# msp432_breakout_i2c.net
KiCad netlist of a schematic drawn in EAGLE
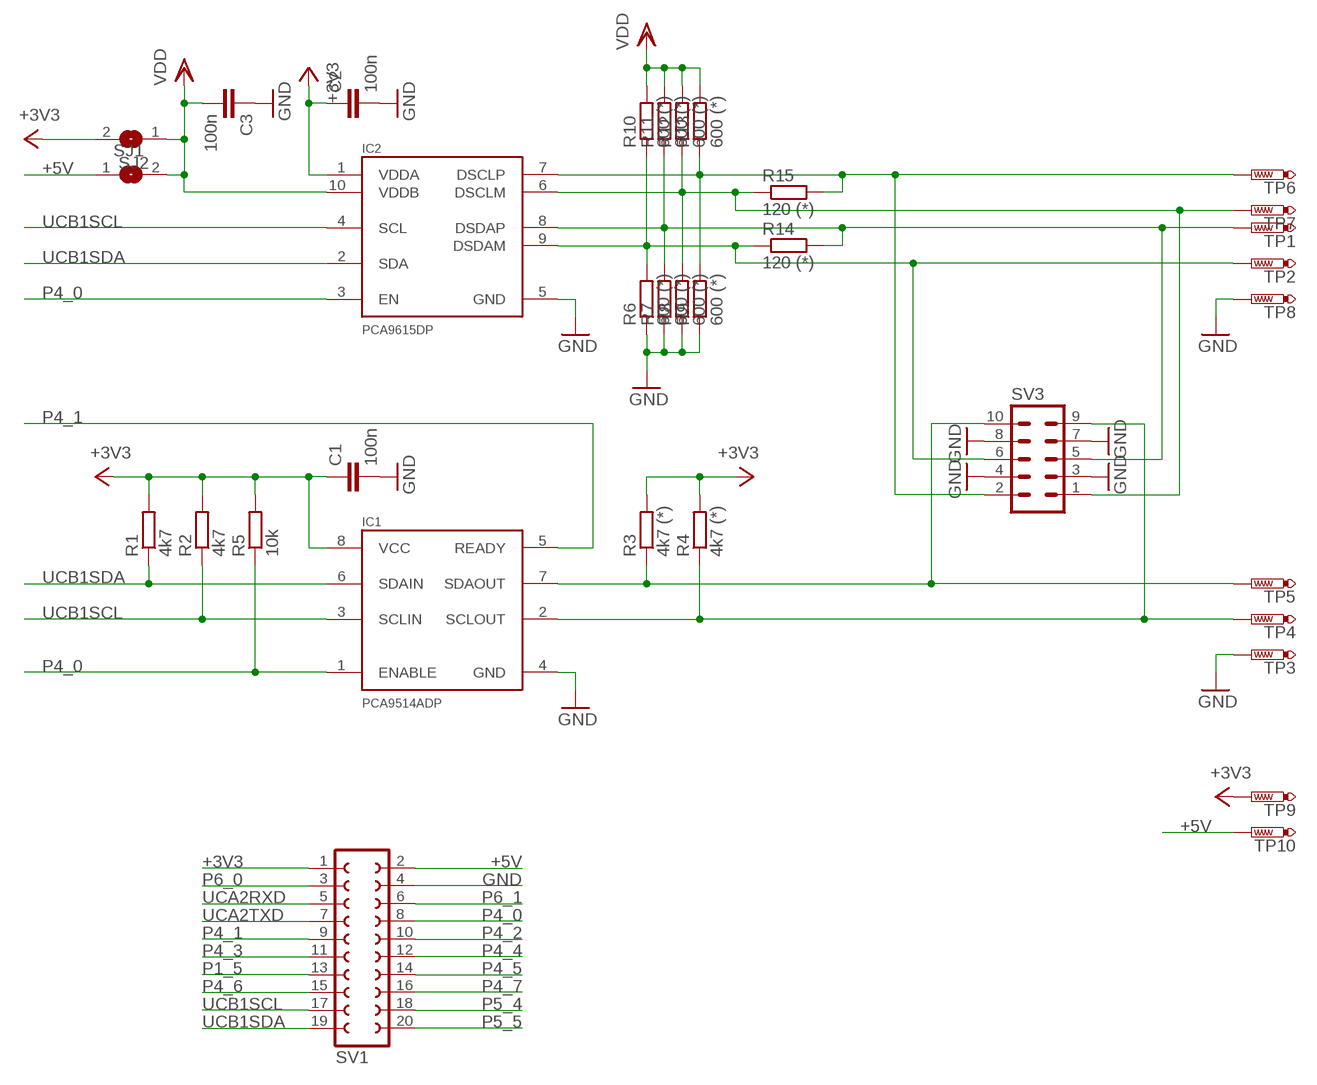
[diagram p0: schematic, sheet 1]

(export (version "E")
  (design (tool "Eeschema 10.0.6"))
  (components
    (comp (ref "C1")
      (value "100n")
      (footprint "eagle-import:C0603")
      (libsource (lib "eagle-import") (part "C-EUC0603"))
    )
    (comp (ref "C2")
      (value "100n")
      (footprint "eagle-import:C0603")
      (libsource (lib "eagle-import") (part "C-EUC0603"))
    )
    (comp (ref "C3")
      (value "100n")
      (footprint "eagle-import:C0603")
      (libsource (lib "eagle-import") (part "C-EUC0603"))
    )
    (comp (ref "IC1")
      (value "PCA9514ADP")
      (footprint "eagle-import:TSSOP8")
      (libsource (lib "eagle-import") (part "PCA9514ADP"))
    )
    (comp (ref "IC2")
      (value "PCA9615DP")
      (footprint "eagle-import:TSSOP10")
      (libsource (lib "eagle-import") (part "PCA9615DP"))
    )
    (comp (ref "R1")
      (value "4k7")
      (footprint "eagle-import:R0603")
      (libsource (lib "eagle-import") (part "R-EU_R0603"))
    )
    (comp (ref "R2")
      (value "4k7")
      (footprint "eagle-import:R0603")
      (libsource (lib "eagle-import") (part "R-EU_R0603"))
    )
    (comp (ref "R3")
      (value "4k7 (*)")
      (footprint "eagle-import:R0603")
      (libsource (lib "eagle-import") (part "R-EU_R0603"))
    )
    (comp (ref "R4")
      (value "4k7 (*)")
      (footprint "eagle-import:R0603")
      (libsource (lib "eagle-import") (part "R-EU_R0603"))
    )
    (comp (ref "R5")
      (value "10k")
      (footprint "eagle-import:R0603")
      (libsource (lib "eagle-import") (part "R-EU_R0603"))
    )
    (comp (ref "R6")
      (value "600 (*)")
      (footprint "eagle-import:R0603")
      (libsource (lib "eagle-import") (part "R-EU_R0603"))
    )
    (comp (ref "R7")
      (value "600 (*)")
      (footprint "eagle-import:R0603")
      (libsource (lib "eagle-import") (part "R-EU_R0603"))
    )
    (comp (ref "R8")
      (value "600 (*)")
      (footprint "eagle-import:R0603")
      (libsource (lib "eagle-import") (part "R-EU_R0603"))
    )
    (comp (ref "R9")
      (value "600 (*)")
      (footprint "eagle-import:R0603")
      (libsource (lib "eagle-import") (part "R-EU_R0603"))
    )
    (comp (ref "R10")
      (value "600 (*)")
      (footprint "eagle-import:R0603")
      (libsource (lib "eagle-import") (part "R-EU_R0603"))
    )
    (comp (ref "R11")
      (value "600 (*)")
      (footprint "eagle-import:R0603")
      (libsource (lib "eagle-import") (part "R-EU_R0603"))
    )
    (comp (ref "R12")
      (value "600 (*)")
      (footprint "eagle-import:R0603")
      (libsource (lib "eagle-import") (part "R-EU_R0603"))
    )
    (comp (ref "R13")
      (value "600 (*)")
      (footprint "eagle-import:R0603")
      (libsource (lib "eagle-import") (part "R-EU_R0603"))
    )
    (comp (ref "R14")
      (value "120 (*)")
      (footprint "eagle-import:R0603")
      (libsource (lib "eagle-import") (part "R-EU_R0603"))
    )
    (comp (ref "R15")
      (value "120 (*)")
      (footprint "eagle-import:R0603")
      (libsource (lib "eagle-import") (part "R-EU_R0603"))
    )
    (comp (ref "SJ1") (value "SJ") (footprint "eagle-import:SJ") (libsource (lib "eagle-import") (part "SJ")))
    (comp (ref "SJ2") (value "SJ") (footprint "eagle-import:SJ") (libsource (lib "eagle-import") (part "SJ")))
    (comp (ref "SV1")
      (value "FE10-2")
      (footprint "eagle-import:FE10-2")
      (libsource (lib "eagle-import") (part "FE10-2"))
    )
    (comp (ref "SV3")
      (value "ML10")
      (footprint "eagle-import:ML10")
      (libsource (lib "eagle-import") (part "ML10"))
    )
    (comp (ref "TP1")
      (value "DSDAP")
      (footprint "eagle-import:P1-17")
      (libsource (lib "eagle-import") (part "PTR1PAD1-17"))
    )
    (comp (ref "TP2")
      (value "DSDAM")
      (footprint "eagle-import:P1-17")
      (libsource (lib "eagle-import") (part "PTR1PAD1-17"))
    )
    (comp (ref "TP3")
      (value "GND")
      (footprint "eagle-import:P1-17")
      (libsource (lib "eagle-import") (part "PTR1PAD1-17"))
    )
    (comp (ref "TP4")
      (value "SCLOUT")
      (footprint "eagle-import:P1-17")
      (libsource (lib "eagle-import") (part "PTR1PAD1-17"))
    )
    (comp (ref "TP5")
      (value "SDAOUT")
      (footprint "eagle-import:P1-17")
      (libsource (lib "eagle-import") (part "PTR1PAD1-17"))
    )
    (comp (ref "TP6")
      (value "DSCLP")
      (footprint "eagle-import:P1-17")
      (libsource (lib "eagle-import") (part "PTR1PAD1-17"))
    )
    (comp (ref "TP7")
      (value "DSCLM")
      (footprint "eagle-import:P1-17")
      (libsource (lib "eagle-import") (part "PTR1PAD1-17"))
    )
    (comp (ref "TP8")
      (value "GND")
      (footprint "eagle-import:P1-17")
      (libsource (lib "eagle-import") (part "PTR1PAD1-17"))
    )
    (comp (ref "TP9")
      (value "3V3")
      (footprint "eagle-import:P1-17")
      (libsource (lib "eagle-import") (part "PTR1PAD1-17"))
    )
    (comp (ref "TP10")
      (value "5V")
      (footprint "eagle-import:P1-17")
      (libsource (lib "eagle-import") (part "PTR1PAD1-17"))
    )
  )
  (nets
    (net (code "1") (name "+3V3") (class "Default")
      (node (ref "C1") (pin "1") (pinfunction "1_1") (pintype "passive"))
      (node (ref "C2") (pin "1") (pinfunction "1_1") (pintype "passive"))
      (node (ref "IC1") (pin "8") (pinfunction "VCC_8") (pintype "power_in"))
      (node (ref "IC2") (pin "1") (pinfunction "VDDA_1") (pintype "power_in"))
      (node (ref "R1") (pin "2") (pinfunction "2_2") (pintype "passive"))
      (node (ref "R2") (pin "2") (pinfunction "2_2") (pintype "passive"))
      (node (ref "R3") (pin "2") (pinfunction "2_2") (pintype "passive"))
      (node (ref "R4") (pin "2") (pinfunction "2_2") (pintype "passive"))
      (node (ref "R5") (pin "2") (pinfunction "2_2") (pintype "passive"))
      (node (ref "SJ2") (pin "2") (pinfunction "2_2") (pintype "passive"))
      (node (ref "SV1") (pin "1") (pinfunction "1_1") (pintype "passive"))
      (node (ref "TP9") (pin "TP") (pinfunction "TP_TP") (pintype "input"))
    )
    (net (code "2") (name "/+5V") (class "Default")
      (node (ref "SJ1") (pin "1") (pinfunction "1_1") (pintype "passive"))
      (node (ref "SV1") (pin "2") (pinfunction "2_2") (pintype "passive"))
      (node (ref "TP10") (pin "TP") (pinfunction "TP_TP") (pintype "input"))
    )
    (net (code "3") (name "/P1_5") (class "Default")
      (node (ref "SV1") (pin "13") (pinfunction "13_13") (pintype "passive"))
    )
    (net (code "4") (name "/P4_0") (class "Default")
      (node (ref "IC1") (pin "1") (pinfunction "ENABLE_1") (pintype "bidirectional"))
      (node (ref "IC2") (pin "3") (pinfunction "EN_3") (pintype "bidirectional"))
      (node (ref "R5") (pin "1") (pinfunction "1_1") (pintype "passive"))
      (node (ref "SV1") (pin "8") (pinfunction "8_8") (pintype "passive"))
    )
    (net (code "5") (name "/P4_1") (class "Default")
      (node (ref "IC1") (pin "5") (pinfunction "READY_5") (pintype "bidirectional"))
      (node (ref "SV1") (pin "9") (pinfunction "9_9") (pintype "passive"))
    )
    (net (code "6") (name "/P4_2") (class "Default")
      (node (ref "SV1") (pin "10") (pinfunction "10_10") (pintype "passive"))
    )
    (net (code "7") (name "/P4_3") (class "Default")
      (node (ref "SV1") (pin "11") (pinfunction "11_11") (pintype "passive"))
    )
    (net (code "8") (name "/P4_4") (class "Default")
      (node (ref "SV1") (pin "12") (pinfunction "12_12") (pintype "passive"))
    )
    (net (code "9") (name "/P4_5") (class "Default")
      (node (ref "SV1") (pin "14") (pinfunction "14_14") (pintype "passive"))
    )
    (net (code "10") (name "/P4_6") (class "Default")
      (node (ref "SV1") (pin "15") (pinfunction "15_15") (pintype "passive"))
    )
    (net (code "11") (name "/P4_7") (class "Default")
      (node (ref "SV1") (pin "16") (pinfunction "16_16") (pintype "passive"))
    )
    (net (code "12") (name "/P5_4") (class "Default")
      (node (ref "SV1") (pin "18") (pinfunction "18_18") (pintype "passive"))
    )
    (net (code "13") (name "/P5_5") (class "Default")
      (node (ref "SV1") (pin "20") (pinfunction "20_20") (pintype "passive"))
    )
    (net (code "14") (name "/P6_0") (class "Default")
      (node (ref "SV1") (pin "3") (pinfunction "3_3") (pintype "passive"))
    )
    (net (code "15") (name "/P6_1") (class "Default")
      (node (ref "SV1") (pin "6") (pinfunction "6_6") (pintype "passive"))
    )
    (net (code "16") (name "/UCA2RXD") (class "Default")
      (node (ref "SV1") (pin "5") (pinfunction "5_5") (pintype "passive"))
    )
    (net (code "17") (name "/UCA2TXD") (class "Default")
      (node (ref "SV1") (pin "7") (pinfunction "7_7") (pintype "passive"))
    )
    (net (code "18") (name "/UCB1SCL") (class "Default")
      (node (ref "IC1") (pin "3") (pinfunction "SCLIN_3") (pintype "bidirectional"))
      (node (ref "IC2") (pin "4") (pinfunction "SCL_4") (pintype "bidirectional"))
      (node (ref "R2") (pin "1") (pinfunction "1_1") (pintype "passive"))
      (node (ref "SV1") (pin "17") (pinfunction "17_17") (pintype "passive"))
    )
    (net (code "19") (name "/UCB1SDA") (class "Default")
      (node (ref "IC1") (pin "6") (pinfunction "SDAIN_6") (pintype "bidirectional"))
      (node (ref "IC2") (pin "2") (pinfunction "SDA_2") (pintype "bidirectional"))
      (node (ref "R1") (pin "1") (pinfunction "1_1") (pintype "passive"))
      (node (ref "SV1") (pin "19") (pinfunction "19_19") (pintype "passive"))
    )
    (net (code "20") (name "GND") (class "Default")
      (node (ref "C1") (pin "2") (pinfunction "2_2") (pintype "passive"))
      (node (ref "C2") (pin "2") (pinfunction "2_2") (pintype "passive"))
      (node (ref "C3") (pin "1") (pinfunction "1_1") (pintype "passive"))
      (node (ref "IC1") (pin "4") (pinfunction "GND_4") (pintype "power_in"))
      (node (ref "IC2") (pin "5") (pinfunction "GND_5") (pintype "power_in"))
      (node (ref "R6") (pin "1") (pinfunction "1_1") (pintype "passive"))
      (node (ref "R7") (pin "1") (pinfunction "1_1") (pintype "passive"))
      (node (ref "R8") (pin "1") (pinfunction "1_1") (pintype "passive"))
      (node (ref "R9") (pin "1") (pinfunction "1_1") (pintype "passive"))
      (node (ref "SV1") (pin "4") (pinfunction "4_4") (pintype "passive"))
      (node (ref "SV3") (pin "3") (pinfunction "3_3") (pintype "passive"))
      (node (ref "SV3") (pin "4") (pinfunction "4_4") (pintype "passive"))
      (node (ref "SV3") (pin "7") (pinfunction "7_7") (pintype "passive"))
      (node (ref "SV3") (pin "8") (pinfunction "8_8") (pintype "passive"))
      (node (ref "TP3") (pin "TP") (pinfunction "TP_TP") (pintype "input"))
      (node (ref "TP8") (pin "TP") (pinfunction "TP_TP") (pintype "input"))
    )
    (net (code "21") (name "Net-(IC1-SCLOUT)") (class "Default")
      (node (ref "IC1") (pin "2") (pinfunction "SCLOUT_2") (pintype "bidirectional"))
      (node (ref "R4") (pin "1") (pinfunction "1_1") (pintype "passive"))
      (node (ref "SV3") (pin "9") (pinfunction "9_9") (pintype "passive"))
      (node (ref "TP4") (pin "TP") (pinfunction "TP_TP") (pintype "input"))
    )
    (net (code "22") (name "Net-(IC1-SDAOUT)") (class "Default")
      (node (ref "IC1") (pin "7") (pinfunction "SDAOUT_7") (pintype "bidirectional"))
      (node (ref "R3") (pin "1") (pinfunction "1_1") (pintype "passive"))
      (node (ref "SV3") (pin "10") (pinfunction "10_10") (pintype "passive"))
      (node (ref "TP5") (pin "TP") (pinfunction "TP_TP") (pintype "input"))
    )
    (net (code "23") (name "Net-(IC2-DSCLM)") (class "Default")
      (node (ref "IC2") (pin "6") (pinfunction "DSCLM_6") (pintype "bidirectional"))
      (node (ref "R12") (pin "1") (pinfunction "1_1") (pintype "passive"))
      (node (ref "R15") (pin "1") (pinfunction "1_1") (pintype "passive"))
      (node (ref "R8") (pin "2") (pinfunction "2_2") (pintype "passive"))
      (node (ref "SV3") (pin "1") (pinfunction "1_1") (pintype "passive"))
      (node (ref "TP7") (pin "TP") (pinfunction "TP_TP") (pintype "input"))
    )
    (net (code "24") (name "Net-(IC2-DSCLP)") (class "Default")
      (node (ref "IC2") (pin "7") (pinfunction "DSCLP_7") (pintype "bidirectional"))
      (node (ref "R13") (pin "1") (pinfunction "1_1") (pintype "passive"))
      (node (ref "R15") (pin "2") (pinfunction "2_2") (pintype "passive"))
      (node (ref "R9") (pin "2") (pinfunction "2_2") (pintype "passive"))
      (node (ref "SV3") (pin "2") (pinfunction "2_2") (pintype "passive"))
      (node (ref "TP6") (pin "TP") (pinfunction "TP_TP") (pintype "input"))
    )
    (net (code "25") (name "Net-(IC2-DSDAM)") (class "Default")
      (node (ref "IC2") (pin "9") (pinfunction "DSDAM_9") (pintype "bidirectional"))
      (node (ref "R10") (pin "1") (pinfunction "1_1") (pintype "passive"))
      (node (ref "R14") (pin "1") (pinfunction "1_1") (pintype "passive"))
      (node (ref "R6") (pin "2") (pinfunction "2_2") (pintype "passive"))
      (node (ref "SV3") (pin "6") (pinfunction "6_6") (pintype "passive"))
      (node (ref "TP2") (pin "TP") (pinfunction "TP_TP") (pintype "input"))
    )
    (net (code "26") (name "Net-(IC2-DSDAP)") (class "Default")
      (node (ref "IC2") (pin "8") (pinfunction "DSDAP_8") (pintype "bidirectional"))
      (node (ref "R11") (pin "1") (pinfunction "1_1") (pintype "passive"))
      (node (ref "R14") (pin "2") (pinfunction "2_2") (pintype "passive"))
      (node (ref "R7") (pin "2") (pinfunction "2_2") (pintype "passive"))
      (node (ref "SV3") (pin "5") (pinfunction "5_5") (pintype "passive"))
      (node (ref "TP1") (pin "TP") (pinfunction "TP_TP") (pintype "input"))
    )
    (net (code "27") (name "VDD") (class "Default")
      (node (ref "C3") (pin "2") (pinfunction "2_2") (pintype "passive"))
      (node (ref "IC2") (pin "10") (pinfunction "VDDB_10") (pintype "power_in"))
      (node (ref "R10") (pin "2") (pinfunction "2_2") (pintype "passive"))
      (node (ref "R11") (pin "2") (pinfunction "2_2") (pintype "passive"))
      (node (ref "R12") (pin "2") (pinfunction "2_2") (pintype "passive"))
      (node (ref "R13") (pin "2") (pinfunction "2_2") (pintype "passive"))
      (node (ref "SJ1") (pin "2") (pinfunction "2_2") (pintype "passive"))
      (node (ref "SJ2") (pin "1") (pinfunction "1_1") (pintype "passive"))
    )
  )
)
